# monitoring_2.net
KiCad netlist of a schematic drawn in EAGLE
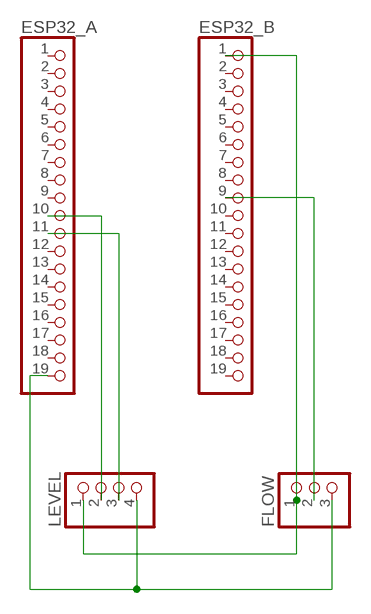
[diagram p0: schematic, sheet 1]

(export (version "E")
  (design (tool "Eeschema 10.0.6"))
  (components
    (comp (ref "ESP32_A")
      (value "PINHD-1X19")
      (footprint "eagle-import:1X19")
      (libsource (lib "eagle-import") (part "PINHD-1X19"))
    )
    (comp (ref "ESP32_B")
      (value "PINHD-1X19")
      (footprint "eagle-import:1X19")
      (libsource (lib "eagle-import") (part "PINHD-1X19"))
    )
    (comp (ref "FLOW")
      (value "PINHD-1X3")
      (footprint "eagle-import:1X03")
      (libsource (lib "eagle-import") (part "PINHD-1X3"))
    )
    (comp (ref "LEVEL")
      (value "PINHD-1X4")
      (footprint "eagle-import:1X04")
      (libsource (lib "eagle-import") (part "PINHD-1X4"))
    )
  )
  (nets
    (net (code "1") (name "Net-(ESP32_A-Pad10)") (class "Default")
      (node (ref "ESP32_A") (pin "10") (pinfunction "10_10") (pintype "passive"))
      (node (ref "LEVEL") (pin "2") (pinfunction "2_2") (pintype "passive"))
    )
    (net (code "2") (name "Net-(ESP32_A-Pad11)") (class "Default")
      (node (ref "ESP32_A") (pin "11") (pinfunction "11_11") (pintype "passive"))
      (node (ref "LEVEL") (pin "3") (pinfunction "3_3") (pintype "passive"))
    )
    (net (code "3") (name "Net-(ESP32_A-Pad19)") (class "Default")
      (node (ref "ESP32_A") (pin "19") (pinfunction "19_19") (pintype "passive"))
      (node (ref "FLOW") (pin "3") (pinfunction "3_3") (pintype "passive"))
      (node (ref "LEVEL") (pin "4") (pinfunction "4_4") (pintype "passive"))
    )
    (net (code "4") (name "Net-(ESP32_B-Pad1)") (class "Default")
      (node (ref "ESP32_B") (pin "1") (pinfunction "1_1") (pintype "passive"))
      (node (ref "FLOW") (pin "1") (pinfunction "1_1") (pintype "passive"))
      (node (ref "LEVEL") (pin "1") (pinfunction "1_1") (pintype "passive"))
    )
    (net (code "5") (name "Net-(ESP32_B-Pad9)") (class "Default")
      (node (ref "ESP32_B") (pin "9") (pinfunction "9_9") (pintype "passive"))
      (node (ref "FLOW") (pin "2") (pinfunction "2_2") (pintype "passive"))
    )
    (net (code "6") (name "unconnected-(ESP32_A-Pad1)") (class "Default")
      (node (ref "ESP32_A") (pin "1") (pinfunction "1_1") (pintype "passive"))
    )
    (net (code "7") (name "unconnected-(ESP32_A-Pad2)") (class "Default")
      (node (ref "ESP32_A") (pin "2") (pinfunction "2_2") (pintype "passive"))
    )
    (net (code "8") (name "unconnected-(ESP32_A-Pad3)") (class "Default")
      (node (ref "ESP32_A") (pin "3") (pinfunction "3_3") (pintype "passive"))
    )
    (net (code "9") (name "unconnected-(ESP32_A-Pad4)") (class "Default")
      (node (ref "ESP32_A") (pin "4") (pinfunction "4_4") (pintype "passive"))
    )
    (net (code "10") (name "unconnected-(ESP32_A-Pad5)") (class "Default")
      (node (ref "ESP32_A") (pin "5") (pinfunction "5_5") (pintype "passive"))
    )
    (net (code "11") (name "unconnected-(ESP32_A-Pad6)") (class "Default")
      (node (ref "ESP32_A") (pin "6") (pinfunction "6_6") (pintype "passive"))
    )
    (net (code "12") (name "unconnected-(ESP32_A-Pad7)") (class "Default")
      (node (ref "ESP32_A") (pin "7") (pinfunction "7_7") (pintype "passive"))
    )
    (net (code "13") (name "unconnected-(ESP32_A-Pad8)") (class "Default")
      (node (ref "ESP32_A") (pin "8") (pinfunction "8_8") (pintype "passive"))
    )
    (net (code "14") (name "unconnected-(ESP32_A-Pad9)") (class "Default")
      (node (ref "ESP32_A") (pin "9") (pinfunction "9_9") (pintype "passive"))
    )
    (net (code "15") (name "unconnected-(ESP32_A-Pad12)") (class "Default")
      (node (ref "ESP32_A") (pin "12") (pinfunction "12_12") (pintype "passive"))
    )
    (net (code "16") (name "unconnected-(ESP32_A-Pad13)") (class "Default")
      (node (ref "ESP32_A") (pin "13") (pinfunction "13_13") (pintype "passive"))
    )
    (net (code "17") (name "unconnected-(ESP32_A-Pad14)") (class "Default")
      (node (ref "ESP32_A") (pin "14") (pinfunction "14_14") (pintype "passive"))
    )
    (net (code "18") (name "unconnected-(ESP32_A-Pad15)") (class "Default")
      (node (ref "ESP32_A") (pin "15") (pinfunction "15_15") (pintype "passive"))
    )
    (net (code "19") (name "unconnected-(ESP32_A-Pad16)") (class "Default")
      (node (ref "ESP32_A") (pin "16") (pinfunction "16_16") (pintype "passive"))
    )
    (net (code "20") (name "unconnected-(ESP32_A-Pad17)") (class "Default")
      (node (ref "ESP32_A") (pin "17") (pinfunction "17_17") (pintype "passive"))
    )
    (net (code "21") (name "unconnected-(ESP32_A-Pad18)") (class "Default")
      (node (ref "ESP32_A") (pin "18") (pinfunction "18_18") (pintype "passive"))
    )
    (net (code "22") (name "unconnected-(ESP32_B-Pad2)") (class "Default")
      (node (ref "ESP32_B") (pin "2") (pinfunction "2_2") (pintype "passive"))
    )
    (net (code "23") (name "unconnected-(ESP32_B-Pad3)") (class "Default")
      (node (ref "ESP32_B") (pin "3") (pinfunction "3_3") (pintype "passive"))
    )
    (net (code "24") (name "unconnected-(ESP32_B-Pad4)") (class "Default")
      (node (ref "ESP32_B") (pin "4") (pinfunction "4_4") (pintype "passive"))
    )
    (net (code "25") (name "unconnected-(ESP32_B-Pad5)") (class "Default")
      (node (ref "ESP32_B") (pin "5") (pinfunction "5_5") (pintype "passive"))
    )
    (net (code "26") (name "unconnected-(ESP32_B-Pad6)") (class "Default")
      (node (ref "ESP32_B") (pin "6") (pinfunction "6_6") (pintype "passive"))
    )
    (net (code "27") (name "unconnected-(ESP32_B-Pad7)") (class "Default")
      (node (ref "ESP32_B") (pin "7") (pinfunction "7_7") (pintype "passive"))
    )
    (net (code "28") (name "unconnected-(ESP32_B-Pad8)") (class "Default")
      (node (ref "ESP32_B") (pin "8") (pinfunction "8_8") (pintype "passive"))
    )
    (net (code "29") (name "unconnected-(ESP32_B-Pad10)") (class "Default")
      (node (ref "ESP32_B") (pin "10") (pinfunction "10_10") (pintype "passive"))
    )
    (net (code "30") (name "unconnected-(ESP32_B-Pad11)") (class "Default")
      (node (ref "ESP32_B") (pin "11") (pinfunction "11_11") (pintype "passive"))
    )
    (net (code "31") (name "unconnected-(ESP32_B-Pad12)") (class "Default")
      (node (ref "ESP32_B") (pin "12") (pinfunction "12_12") (pintype "passive"))
    )
    (net (code "32") (name "unconnected-(ESP32_B-Pad13)") (class "Default")
      (node (ref "ESP32_B") (pin "13") (pinfunction "13_13") (pintype "passive"))
    )
    (net (code "33") (name "unconnected-(ESP32_B-Pad14)") (class "Default")
      (node (ref "ESP32_B") (pin "14") (pinfunction "14_14") (pintype "passive"))
    )
    (net (code "34") (name "unconnected-(ESP32_B-Pad15)") (class "Default")
      (node (ref "ESP32_B") (pin "15") (pinfunction "15_15") (pintype "passive"))
    )
    (net (code "35") (name "unconnected-(ESP32_B-Pad16)") (class "Default")
      (node (ref "ESP32_B") (pin "16") (pinfunction "16_16") (pintype "passive"))
    )
    (net (code "36") (name "unconnected-(ESP32_B-Pad17)") (class "Default")
      (node (ref "ESP32_B") (pin "17") (pinfunction "17_17") (pintype "passive"))
    )
    (net (code "37") (name "unconnected-(ESP32_B-Pad18)") (class "Default")
      (node (ref "ESP32_B") (pin "18") (pinfunction "18_18") (pintype "passive"))
    )
    (net (code "38") (name "unconnected-(ESP32_B-Pad19)") (class "Default")
      (node (ref "ESP32_B") (pin "19") (pinfunction "19_19") (pintype "passive"))
    )
  )
)
